# encoders.net
KiCad netlist of a schematic drawn in EAGLE
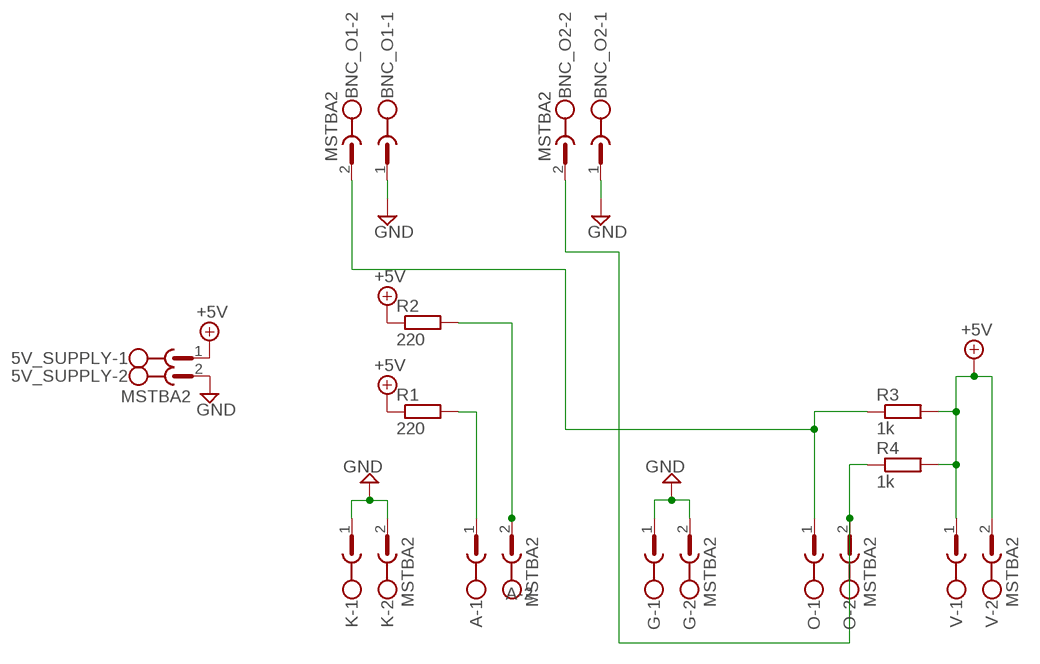
[diagram p0: schematic, sheet 1]

(export (version "E")
  (design (tool "Eeschema 10.0.6"))
  (components
    (comp (ref "5V_SUPPLY")
      (value "MSTBA2")
      (footprint "eagle-import:MSTBA2")
      (fields (field (name "MF") "FARNELL") (field (name "MPN") "1757242"))
      (libsource (lib "eagle-import") (part "MSTBA2"))
    )
    (comp (ref "A")
      (value "MSTBA2")
      (footprint "eagle-import:MSTBA2")
      (fields (field (name "MF") "FARNELL") (field (name "MPN") "1757242"))
      (libsource (lib "eagle-import") (part "MSTBA2"))
    )
    (comp (ref "BNC_O1")
      (value "MSTBA2")
      (footprint "eagle-import:MSTBA2")
      (fields (field (name "MF") "FARNELL") (field (name "MPN") "1757242"))
      (libsource (lib "eagle-import") (part "MSTBA2"))
    )
    (comp (ref "BNC_O2")
      (value "MSTBA2")
      (footprint "eagle-import:MSTBA2")
      (fields (field (name "MF") "FARNELL") (field (name "MPN") "1757242"))
      (libsource (lib "eagle-import") (part "MSTBA2"))
    )
    (comp (ref "G")
      (value "MSTBA2")
      (footprint "eagle-import:MSTBA2")
      (fields (field (name "MF") "FARNELL") (field (name "MPN") "1757242"))
      (libsource (lib "eagle-import") (part "MSTBA2"))
    )
    (comp (ref "K")
      (value "MSTBA2")
      (footprint "eagle-import:MSTBA2")
      (fields (field (name "MF") "FARNELL") (field (name "MPN") "1757242"))
      (libsource (lib "eagle-import") (part "MSTBA2"))
    )
    (comp (ref "O")
      (value "MSTBA2")
      (footprint "eagle-import:MSTBA2")
      (fields (field (name "MF") "FARNELL") (field (name "MPN") "1757242"))
      (libsource (lib "eagle-import") (part "MSTBA2"))
    )
    (comp (ref "R1")
      (value "220")
      (footprint "eagle-import:0204_7")
      (libsource (lib "eagle-import") (part "R-EU_0204/7"))
    )
    (comp (ref "R2")
      (value "220")
      (footprint "eagle-import:0204_7")
      (libsource (lib "eagle-import") (part "R-EU_0204/7"))
    )
    (comp (ref "R3")
      (value "1k")
      (footprint "eagle-import:0204_7")
      (libsource (lib "eagle-import") (part "R-EU_0204/7"))
    )
    (comp (ref "R4")
      (value "1k")
      (footprint "eagle-import:0204_7")
      (libsource (lib "eagle-import") (part "R-EU_0204/7"))
    )
    (comp (ref "V")
      (value "MSTBA2")
      (footprint "eagle-import:MSTBA2")
      (fields (field (name "MF") "FARNELL") (field (name "MPN") "1757242"))
      (libsource (lib "eagle-import") (part "MSTBA2"))
    )
  )
  (nets
    (net (code "1") (name "+5V") (class "Default")
      (node (ref "5V_SUPPLY") (pin "1") (pinfunction "1_1") (pintype "passive"))
      (node (ref "R1") (pin "1") (pinfunction "1_1") (pintype "passive"))
      (node (ref "R2") (pin "1") (pinfunction "1_1") (pintype "passive"))
      (node (ref "R3") (pin "2") (pinfunction "2_2") (pintype "passive"))
      (node (ref "R4") (pin "2") (pinfunction "2_2") (pintype "passive"))
      (node (ref "V") (pin "1") (pinfunction "1_1") (pintype "passive"))
      (node (ref "V") (pin "2") (pinfunction "1_2") (pintype "passive"))
    )
    (net (code "2") (name "GND") (class "Default")
      (node (ref "5V_SUPPLY") (pin "2") (pinfunction "1_2") (pintype "passive"))
      (node (ref "BNC_O1") (pin "1") (pinfunction "1_1") (pintype "passive"))
      (node (ref "BNC_O2") (pin "1") (pinfunction "1_1") (pintype "passive"))
      (node (ref "G") (pin "1") (pinfunction "1_1") (pintype "passive"))
      (node (ref "G") (pin "2") (pinfunction "1_2") (pintype "passive"))
      (node (ref "K") (pin "1") (pinfunction "1_1") (pintype "passive"))
      (node (ref "K") (pin "2") (pinfunction "1_2") (pintype "passive"))
    )
    (net (code "3") (name "Net-(A-Pad1)") (class "Default")
      (node (ref "A") (pin "1") (pinfunction "1_1") (pintype "passive"))
      (node (ref "R1") (pin "2") (pinfunction "2_2") (pintype "passive"))
    )
    (net (code "4") (name "Net-(AB-1)") (class "Default")
      (node (ref "A") (pin "2") (pinfunction "1_2") (pintype "passive"))
      (node (ref "R2") (pin "2") (pinfunction "2_2") (pintype "passive"))
    )
    (net (code "5") (name "Net-(BNC_O1B-1)") (class "Default")
      (node (ref "BNC_O1") (pin "2") (pinfunction "1_2") (pintype "passive"))
      (node (ref "O") (pin "1") (pinfunction "1_1") (pintype "passive"))
      (node (ref "R3") (pin "1") (pinfunction "1_1") (pintype "passive"))
    )
    (net (code "6") (name "Net-(BNC_O2B-1)") (class "Default")
      (node (ref "BNC_O2") (pin "2") (pinfunction "1_2") (pintype "passive"))
      (node (ref "O") (pin "2") (pinfunction "1_2") (pintype "passive"))
      (node (ref "R4") (pin "1") (pinfunction "1_1") (pintype "passive"))
    )
  )
)
